# Decap.net
KiCad netlist of a schematic drawn in Altium Designer
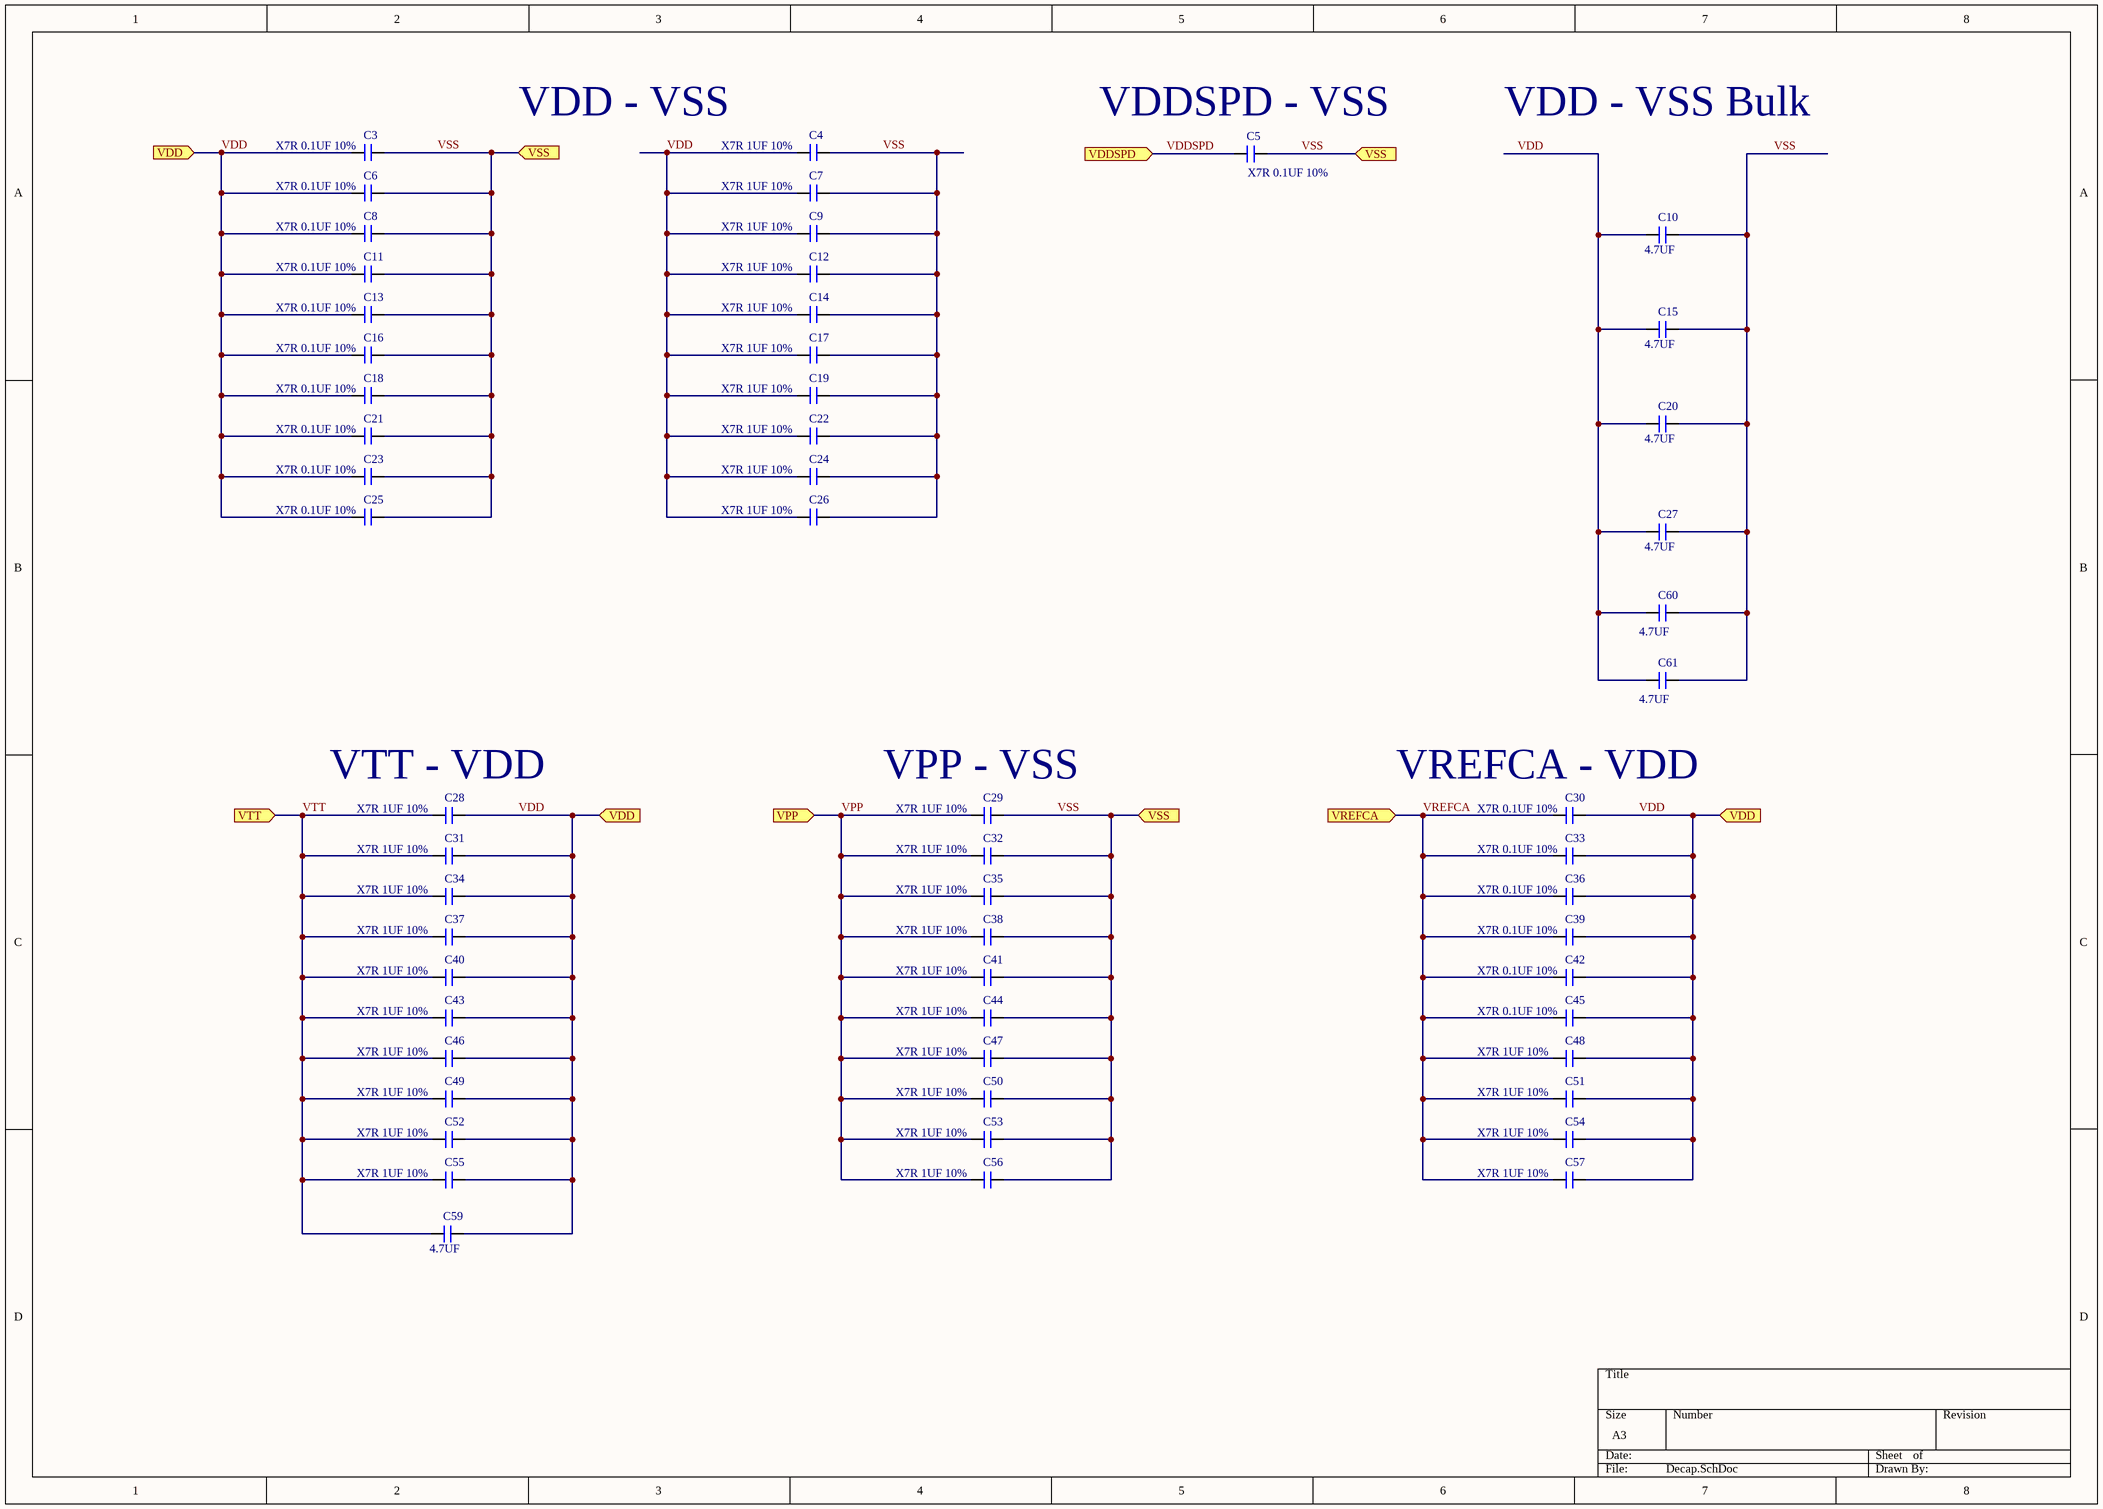
[diagram p0: Decap.SchDoc]

(export (version "E")
  (design (tool "Eeschema 10.0.6"))
  (components
    (comp (ref "C3")
      (value "Capacitor 0402")
      (footprint "Capacitor 0402")
      (fields
        (field (name "MANUFACTURER") "Vishay")
        (field (name "MANUFACTURER PART NUMBER") "CRCW060310K0FKEA")
        (field (name "TOLERANCE") "1%")
        (field (name "CAPACITANCE") "X7R 0.1UF 10%")
      )
      (libsource (lib "RouterIntLib") (part "Capacitor 0201"))
    )
    (comp (ref "C4")
      (value "Capacitor 0402")
      (footprint "Capacitor 0402")
      (fields
        (field (name "MANUFACTURER") "Vishay")
        (field (name "MANUFACTURER PART NUMBER") "CRCW060310K0FKEA")
        (field (name "TOLERANCE") "1%")
        (field (name "CAPACITANCE") "X7R 1UF 10%")
      )
      (libsource (lib "RouterIntLib") (part "Capacitor 0201"))
    )
    (comp (ref "C5")
      (value "Capacitor 0402")
      (footprint "Capacitor 0402")
      (fields
        (field (name "MANUFACTURER") "Vishay")
        (field (name "MANUFACTURER PART NUMBER") "CRCW060310K0FKEA")
        (field (name "TOLERANCE") "1%")
        (field (name "CAPACITANCE") "X7R 0.1UF 10%")
      )
      (libsource (lib "RouterIntLib") (part "Capacitor 0201"))
    )
    (comp (ref "C6")
      (value "Capacitor 0402")
      (footprint "Capacitor 0402")
      (fields
        (field (name "MANUFACTURER") "Vishay")
        (field (name "MANUFACTURER PART NUMBER") "CRCW060310K0FKEA")
        (field (name "TOLERANCE") "1%")
        (field (name "CAPACITANCE") "X7R 0.1UF 10%")
      )
      (libsource (lib "RouterIntLib") (part "Capacitor 0201"))
    )
    (comp (ref "C7")
      (value "Capacitor 0402")
      (footprint "Capacitor 0402")
      (fields
        (field (name "MANUFACTURER") "Vishay")
        (field (name "MANUFACTURER PART NUMBER") "CRCW060310K0FKEA")
        (field (name "TOLERANCE") "1%")
        (field (name "CAPACITANCE") "X7R 1UF 10%")
      )
      (libsource (lib "RouterIntLib") (part "Capacitor 0201"))
    )
    (comp (ref "C8")
      (value "Capacitor 0402")
      (footprint "Capacitor 0402")
      (fields
        (field (name "MANUFACTURER") "Vishay")
        (field (name "MANUFACTURER PART NUMBER") "CRCW060310K0FKEA")
        (field (name "TOLERANCE") "1%")
        (field (name "CAPACITANCE") "X7R 0.1UF 10%")
      )
      (libsource (lib "RouterIntLib") (part "Capacitor 0201"))
    )
    (comp (ref "C9")
      (value "Capacitor 0402")
      (footprint "Capacitor 0402")
      (fields
        (field (name "MANUFACTURER") "Vishay")
        (field (name "MANUFACTURER PART NUMBER") "CRCW060310K0FKEA")
        (field (name "TOLERANCE") "1%")
        (field (name "CAPACITANCE") "X7R 1UF 10%")
      )
      (libsource (lib "RouterIntLib") (part "Capacitor 0201"))
    )
    (comp (ref "C10")
      (value "Capacitor 0603")
      (footprint "Capacitor 0603")
      (fields
        (field (name "MANUFACTURER") "Vishay")
        (field (name "MANUFACTURER PART NUMBER") "CRCW060310K0FKEA")
        (field (name "TOLERANCE") "1%")
        (field (name "CAPACITANCE") "4.7UF")
      )
      (libsource (lib "RouterIntLib") (part "Capacitor 0603"))
    )
    (comp (ref "C11")
      (value "Capacitor 0402")
      (footprint "Capacitor 0402")
      (fields
        (field (name "MANUFACTURER") "Vishay")
        (field (name "MANUFACTURER PART NUMBER") "CRCW060310K0FKEA")
        (field (name "TOLERANCE") "1%")
        (field (name "CAPACITANCE") "X7R 0.1UF 10%")
      )
      (libsource (lib "RouterIntLib") (part "Capacitor 0201"))
    )
    (comp (ref "C12")
      (value "Capacitor 0402")
      (footprint "Capacitor 0402")
      (fields
        (field (name "MANUFACTURER") "Vishay")
        (field (name "MANUFACTURER PART NUMBER") "CRCW060310K0FKEA")
        (field (name "TOLERANCE") "1%")
        (field (name "CAPACITANCE") "X7R 1UF 10%")
      )
      (libsource (lib "RouterIntLib") (part "Capacitor 0201"))
    )
    (comp (ref "C13")
      (value "Capacitor 0402")
      (footprint "Capacitor 0402")
      (fields
        (field (name "MANUFACTURER") "Vishay")
        (field (name "MANUFACTURER PART NUMBER") "CRCW060310K0FKEA")
        (field (name "TOLERANCE") "1%")
        (field (name "CAPACITANCE") "X7R 0.1UF 10%")
      )
      (libsource (lib "RouterIntLib") (part "Capacitor 0201"))
    )
    (comp (ref "C14")
      (value "Capacitor 0402")
      (footprint "Capacitor 0402")
      (fields
        (field (name "MANUFACTURER") "Vishay")
        (field (name "MANUFACTURER PART NUMBER") "CRCW060310K0FKEA")
        (field (name "TOLERANCE") "1%")
        (field (name "CAPACITANCE") "X7R 1UF 10%")
      )
      (libsource (lib "RouterIntLib") (part "Capacitor 0201"))
    )
    (comp (ref "C15")
      (value "Capacitor 0603")
      (footprint "Capacitor 0603")
      (fields
        (field (name "MANUFACTURER") "Vishay")
        (field (name "MANUFACTURER PART NUMBER") "CRCW060310K0FKEA")
        (field (name "TOLERANCE") "1%")
        (field (name "CAPACITANCE") "4.7UF")
      )
      (libsource (lib "RouterIntLib") (part "Capacitor 0603"))
    )
    (comp (ref "C16")
      (value "Capacitor 0402")
      (footprint "Capacitor 0402")
      (fields
        (field (name "MANUFACTURER") "Vishay")
        (field (name "MANUFACTURER PART NUMBER") "CRCW060310K0FKEA")
        (field (name "TOLERANCE") "1%")
        (field (name "CAPACITANCE") "X7R 0.1UF 10%")
      )
      (libsource (lib "RouterIntLib") (part "Capacitor 0201"))
    )
    (comp (ref "C17")
      (value "Capacitor 0402")
      (footprint "Capacitor 0402")
      (fields
        (field (name "MANUFACTURER") "Vishay")
        (field (name "MANUFACTURER PART NUMBER") "CRCW060310K0FKEA")
        (field (name "TOLERANCE") "1%")
        (field (name "CAPACITANCE") "X7R 1UF 10%")
      )
      (libsource (lib "RouterIntLib") (part "Capacitor 0201"))
    )
    (comp (ref "C18")
      (value "Capacitor 0402")
      (footprint "Capacitor 0402")
      (fields
        (field (name "MANUFACTURER") "Vishay")
        (field (name "MANUFACTURER PART NUMBER") "CRCW060310K0FKEA")
        (field (name "TOLERANCE") "1%")
        (field (name "CAPACITANCE") "X7R 0.1UF 10%")
      )
      (libsource (lib "RouterIntLib") (part "Capacitor 0201"))
    )
    (comp (ref "C19")
      (value "Capacitor 0402")
      (footprint "Capacitor 0402")
      (fields
        (field (name "MANUFACTURER") "Vishay")
        (field (name "MANUFACTURER PART NUMBER") "CRCW060310K0FKEA")
        (field (name "TOLERANCE") "1%")
        (field (name "CAPACITANCE") "X7R 1UF 10%")
      )
      (libsource (lib "RouterIntLib") (part "Capacitor 0201"))
    )
    (comp (ref "C20")
      (value "Capacitor 0603")
      (footprint "Capacitor 0603")
      (fields
        (field (name "MANUFACTURER") "Vishay")
        (field (name "MANUFACTURER PART NUMBER") "CRCW060310K0FKEA")
        (field (name "TOLERANCE") "1%")
        (field (name "CAPACITANCE") "4.7UF")
      )
      (libsource (lib "RouterIntLib") (part "Capacitor 0603"))
    )
    (comp (ref "C21")
      (value "Capacitor 0402")
      (footprint "Capacitor 0402")
      (fields
        (field (name "MANUFACTURER") "Vishay")
        (field (name "MANUFACTURER PART NUMBER") "CRCW060310K0FKEA")
        (field (name "TOLERANCE") "1%")
        (field (name "CAPACITANCE") "X7R 0.1UF 10%")
      )
      (libsource (lib "RouterIntLib") (part "Capacitor 0201"))
    )
    (comp (ref "C22")
      (value "Capacitor 0402")
      (footprint "Capacitor 0402")
      (fields
        (field (name "MANUFACTURER") "Vishay")
        (field (name "MANUFACTURER PART NUMBER") "CRCW060310K0FKEA")
        (field (name "TOLERANCE") "1%")
        (field (name "CAPACITANCE") "X7R 1UF 10%")
      )
      (libsource (lib "RouterIntLib") (part "Capacitor 0201"))
    )
    (comp (ref "C23")
      (value "Capacitor 0402")
      (footprint "Capacitor 0402")
      (fields
        (field (name "MANUFACTURER") "Vishay")
        (field (name "MANUFACTURER PART NUMBER") "CRCW060310K0FKEA")
        (field (name "TOLERANCE") "1%")
        (field (name "CAPACITANCE") "X7R 0.1UF 10%")
      )
      (libsource (lib "RouterIntLib") (part "Capacitor 0201"))
    )
    (comp (ref "C24")
      (value "Capacitor 0402")
      (footprint "Capacitor 0402")
      (fields
        (field (name "MANUFACTURER") "Vishay")
        (field (name "MANUFACTURER PART NUMBER") "CRCW060310K0FKEA")
        (field (name "TOLERANCE") "1%")
        (field (name "CAPACITANCE") "X7R 1UF 10%")
      )
      (libsource (lib "RouterIntLib") (part "Capacitor 0201"))
    )
    (comp (ref "C25")
      (value "Capacitor 0402")
      (footprint "Capacitor 0402")
      (fields
        (field (name "MANUFACTURER") "Vishay")
        (field (name "MANUFACTURER PART NUMBER") "CRCW060310K0FKEA")
        (field (name "TOLERANCE") "1%")
        (field (name "CAPACITANCE") "X7R 0.1UF 10%")
      )
      (libsource (lib "RouterIntLib") (part "Capacitor 0201"))
    )
    (comp (ref "C26")
      (value "Capacitor 0402")
      (footprint "Capacitor 0402")
      (fields
        (field (name "MANUFACTURER") "Vishay")
        (field (name "MANUFACTURER PART NUMBER") "CRCW060310K0FKEA")
        (field (name "TOLERANCE") "1%")
        (field (name "CAPACITANCE") "X7R 1UF 10%")
      )
      (libsource (lib "RouterIntLib") (part "Capacitor 0201"))
    )
    (comp (ref "C27")
      (value "Capacitor 0603")
      (footprint "Capacitor 0603")
      (fields
        (field (name "MANUFACTURER") "Vishay")
        (field (name "MANUFACTURER PART NUMBER") "CRCW060310K0FKEA")
        (field (name "TOLERANCE") "1%")
        (field (name "CAPACITANCE") "4.7UF")
      )
      (libsource (lib "RouterIntLib") (part "Capacitor 0603"))
    )
    (comp (ref "C28")
      (value "Capacitor 0402")
      (footprint "Capacitor 0402")
      (fields
        (field (name "MANUFACTURER") "Vishay")
        (field (name "MANUFACTURER PART NUMBER") "CRCW060310K0FKEA")
        (field (name "TOLERANCE") "1%")
        (field (name "CAPACITANCE") "X7R 1UF 10%")
      )
      (libsource (lib "RouterIntLib") (part "Capacitor 0201"))
    )
    (comp (ref "C29")
      (value "Capacitor 0402")
      (footprint "Capacitor 0402")
      (fields
        (field (name "MANUFACTURER") "Vishay")
        (field (name "MANUFACTURER PART NUMBER") "CRCW060310K0FKEA")
        (field (name "TOLERANCE") "1%")
        (field (name "CAPACITANCE") "X7R 1UF 10%")
      )
      (libsource (lib "RouterIntLib") (part "Capacitor 0201"))
    )
    (comp (ref "C30")
      (value "Capacitor 0402")
      (footprint "Capacitor 0402")
      (fields
        (field (name "MANUFACTURER") "Vishay")
        (field (name "MANUFACTURER PART NUMBER") "CRCW060310K0FKEA")
        (field (name "TOLERANCE") "1%")
        (field (name "CAPACITANCE") "X7R 0.1UF 10%")
      )
      (libsource (lib "RouterIntLib") (part "Capacitor 0201"))
    )
    (comp (ref "C31")
      (value "Capacitor 0402")
      (footprint "Capacitor 0402")
      (fields
        (field (name "MANUFACTURER") "Vishay")
        (field (name "MANUFACTURER PART NUMBER") "CRCW060310K0FKEA")
        (field (name "TOLERANCE") "1%")
        (field (name "CAPACITANCE") "X7R 1UF 10%")
      )
      (libsource (lib "RouterIntLib") (part "Capacitor 0201"))
    )
    (comp (ref "C32")
      (value "Capacitor 0402")
      (footprint "Capacitor 0402")
      (fields
        (field (name "MANUFACTURER") "Vishay")
        (field (name "MANUFACTURER PART NUMBER") "CRCW060310K0FKEA")
        (field (name "TOLERANCE") "1%")
        (field (name "CAPACITANCE") "X7R 1UF 10%")
      )
      (libsource (lib "RouterIntLib") (part "Capacitor 0201"))
    )
    (comp (ref "C33")
      (value "Capacitor 0402")
      (footprint "Capacitor 0402")
      (fields
        (field (name "MANUFACTURER") "Vishay")
        (field (name "MANUFACTURER PART NUMBER") "CRCW060310K0FKEA")
        (field (name "TOLERANCE") "1%")
        (field (name "CAPACITANCE") "X7R 0.1UF 10%")
      )
      (libsource (lib "RouterIntLib") (part "Capacitor 0201"))
    )
    (comp (ref "C34")
      (value "Capacitor 0402")
      (footprint "Capacitor 0402")
      (fields
        (field (name "MANUFACTURER") "Vishay")
        (field (name "MANUFACTURER PART NUMBER") "CRCW060310K0FKEA")
        (field (name "TOLERANCE") "1%")
        (field (name "CAPACITANCE") "X7R 1UF 10%")
      )
      (libsource (lib "RouterIntLib") (part "Capacitor 0201"))
    )
    (comp (ref "C35")
      (value "Capacitor 0402")
      (footprint "Capacitor 0402")
      (fields
        (field (name "MANUFACTURER") "Vishay")
        (field (name "MANUFACTURER PART NUMBER") "CRCW060310K0FKEA")
        (field (name "TOLERANCE") "1%")
        (field (name "CAPACITANCE") "X7R 1UF 10%")
      )
      (libsource (lib "RouterIntLib") (part "Capacitor 0201"))
    )
    (comp (ref "C36")
      (value "Capacitor 0402")
      (footprint "Capacitor 0402")
      (fields
        (field (name "MANUFACTURER") "Vishay")
        (field (name "MANUFACTURER PART NUMBER") "CRCW060310K0FKEA")
        (field (name "TOLERANCE") "1%")
        (field (name "CAPACITANCE") "X7R 0.1UF 10%")
      )
      (libsource (lib "RouterIntLib") (part "Capacitor 0201"))
    )
    (comp (ref "C37")
      (value "Capacitor 0402")
      (footprint "Capacitor 0402")
      (fields
        (field (name "MANUFACTURER") "Vishay")
        (field (name "MANUFACTURER PART NUMBER") "CRCW060310K0FKEA")
        (field (name "TOLERANCE") "1%")
        (field (name "CAPACITANCE") "X7R 1UF 10%")
      )
      (libsource (lib "RouterIntLib") (part "Capacitor 0201"))
    )
    (comp (ref "C38")
      (value "Capacitor 0402")
      (footprint "Capacitor 0402")
      (fields
        (field (name "MANUFACTURER") "Vishay")
        (field (name "MANUFACTURER PART NUMBER") "CRCW060310K0FKEA")
        (field (name "TOLERANCE") "1%")
        (field (name "CAPACITANCE") "X7R 1UF 10%")
      )
      (libsource (lib "RouterIntLib") (part "Capacitor 0201"))
    )
    (comp (ref "C39")
      (value "Capacitor 0402")
      (footprint "Capacitor 0402")
      (fields
        (field (name "MANUFACTURER") "Vishay")
        (field (name "MANUFACTURER PART NUMBER") "CRCW060310K0FKEA")
        (field (name "TOLERANCE") "1%")
        (field (name "CAPACITANCE") "X7R 0.1UF 10%")
      )
      (libsource (lib "RouterIntLib") (part "Capacitor 0201"))
    )
    (comp (ref "C40")
      (value "Capacitor 0402")
      (footprint "Capacitor 0402")
      (fields
        (field (name "MANUFACTURER") "Vishay")
        (field (name "MANUFACTURER PART NUMBER") "CRCW060310K0FKEA")
        (field (name "TOLERANCE") "1%")
        (field (name "CAPACITANCE") "X7R 1UF 10%")
      )
      (libsource (lib "RouterIntLib") (part "Capacitor 0201"))
    )
    (comp (ref "C41")
      (value "Capacitor 0402")
      (footprint "Capacitor 0402")
      (fields
        (field (name "MANUFACTURER") "Vishay")
        (field (name "MANUFACTURER PART NUMBER") "CRCW060310K0FKEA")
        (field (name "TOLERANCE") "1%")
        (field (name "CAPACITANCE") "X7R 1UF 10%")
      )
      (libsource (lib "RouterIntLib") (part "Capacitor 0201"))
    )
    (comp (ref "C42")
      (value "Capacitor 0402")
      (footprint "Capacitor 0402")
      (fields
        (field (name "MANUFACTURER") "Vishay")
        (field (name "MANUFACTURER PART NUMBER") "CRCW060310K0FKEA")
        (field (name "TOLERANCE") "1%")
        (field (name "CAPACITANCE") "X7R 0.1UF 10%")
      )
      (libsource (lib "RouterIntLib") (part "Capacitor 0201"))
    )
    (comp (ref "C43")
      (value "Capacitor 0402")
      (footprint "Capacitor 0402")
      (fields
        (field (name "MANUFACTURER") "Vishay")
        (field (name "MANUFACTURER PART NUMBER") "CRCW060310K0FKEA")
        (field (name "TOLERANCE") "1%")
        (field (name "CAPACITANCE") "X7R 1UF 10%")
      )
      (libsource (lib "RouterIntLib") (part "Capacitor 0201"))
    )
    (comp (ref "C44")
      (value "Capacitor 0402")
      (footprint "Capacitor 0402")
      (fields
        (field (name "MANUFACTURER") "Vishay")
        (field (name "MANUFACTURER PART NUMBER") "CRCW060310K0FKEA")
        (field (name "TOLERANCE") "1%")
        (field (name "CAPACITANCE") "X7R 1UF 10%")
      )
      (libsource (lib "RouterIntLib") (part "Capacitor 0201"))
    )
    (comp (ref "C45")
      (value "Capacitor 0402")
      (footprint "Capacitor 0402")
      (fields
        (field (name "MANUFACTURER") "Vishay")
        (field (name "MANUFACTURER PART NUMBER") "CRCW060310K0FKEA")
        (field (name "TOLERANCE") "1%")
        (field (name "CAPACITANCE") "X7R 0.1UF 10%")
      )
      (libsource (lib "RouterIntLib") (part "Capacitor 0201"))
    )
    (comp (ref "C46")
      (value "Capacitor 0402")
      (footprint "Capacitor 0402")
      (fields
        (field (name "MANUFACTURER") "Vishay")
        (field (name "MANUFACTURER PART NUMBER") "CRCW060310K0FKEA")
        (field (name "TOLERANCE") "1%")
        (field (name "CAPACITANCE") "X7R 1UF 10%")
      )
      (libsource (lib "RouterIntLib") (part "Capacitor 0201"))
    )
    (comp (ref "C47")
      (value "Capacitor 0402")
      (footprint "Capacitor 0402")
      (fields
        (field (name "MANUFACTURER") "Vishay")
        (field (name "MANUFACTURER PART NUMBER") "CRCW060310K0FKEA")
        (field (name "TOLERANCE") "1%")
        (field (name "CAPACITANCE") "X7R 1UF 10%")
      )
      (libsource (lib "RouterIntLib") (part "Capacitor 0201"))
    )
    (comp (ref "C48")
      (value "Capacitor 0402")
      (footprint "Capacitor 0402")
      (fields
        (field (name "MANUFACTURER") "Vishay")
        (field (name "MANUFACTURER PART NUMBER") "CRCW060310K0FKEA")
        (field (name "TOLERANCE") "1%")
        (field (name "CAPACITANCE") "X7R 1UF 10%")
      )
      (libsource (lib "RouterIntLib") (part "Capacitor 0201"))
    )
    (comp (ref "C49")
      (value "Capacitor 0402")
      (footprint "Capacitor 0402")
      (fields
        (field (name "MANUFACTURER") "Vishay")
        (field (name "MANUFACTURER PART NUMBER") "CRCW060310K0FKEA")
        (field (name "TOLERANCE") "1%")
        (field (name "CAPACITANCE") "X7R 1UF 10%")
      )
      (libsource (lib "RouterIntLib") (part "Capacitor 0201"))
    )
    (comp (ref "C50")
      (value "Capacitor 0402")
      (footprint "Capacitor 0402")
      (fields
        (field (name "MANUFACTURER") "Vishay")
        (field (name "MANUFACTURER PART NUMBER") "CRCW060310K0FKEA")
        (field (name "TOLERANCE") "1%")
        (field (name "CAPACITANCE") "X7R 1UF 10%")
      )
      (libsource (lib "RouterIntLib") (part "Capacitor 0201"))
    )
    (comp (ref "C51")
      (value "Capacitor 0402")
      (footprint "Capacitor 0402")
      (fields
        (field (name "MANUFACTURER") "Vishay")
        (field (name "MANUFACTURER PART NUMBER") "CRCW060310K0FKEA")
        (field (name "TOLERANCE") "1%")
        (field (name "CAPACITANCE") "X7R 1UF 10%")
      )
      (libsource (lib "RouterIntLib") (part "Capacitor 0201"))
    )
    (comp (ref "C52")
      (value "Capacitor 0402")
      (footprint "Capacitor 0402")
      (fields
        (field (name "MANUFACTURER") "Vishay")
        (field (name "MANUFACTURER PART NUMBER") "CRCW060310K0FKEA")
        (field (name "TOLERANCE") "1%")
        (field (name "CAPACITANCE") "X7R 1UF 10%")
      )
      (libsource (lib "RouterIntLib") (part "Capacitor 0201"))
    )
    (comp (ref "C53")
      (value "Capacitor 0402")
      (footprint "Capacitor 0402")
      (fields
        (field (name "MANUFACTURER") "Vishay")
        (field (name "MANUFACTURER PART NUMBER") "CRCW060310K0FKEA")
        (field (name "TOLERANCE") "1%")
        (field (name "CAPACITANCE") "X7R 1UF 10%")
      )
      (libsource (lib "RouterIntLib") (part "Capacitor 0201"))
    )
    (comp (ref "C54")
      (value "Capacitor 0402")
      (footprint "Capacitor 0402")
      (fields
        (field (name "MANUFACTURER") "Vishay")
        (field (name "MANUFACTURER PART NUMBER") "CRCW060310K0FKEA")
        (field (name "TOLERANCE") "1%")
        (field (name "CAPACITANCE") "X7R 1UF 10%")
      )
      (libsource (lib "RouterIntLib") (part "Capacitor 0201"))
    )
    (comp (ref "C55")
      (value "Capacitor 0402")
      (footprint "Capacitor 0402")
      (fields
        (field (name "MANUFACTURER") "Vishay")
        (field (name "MANUFACTURER PART NUMBER") "CRCW060310K0FKEA")
        (field (name "TOLERANCE") "1%")
        (field (name "CAPACITANCE") "X7R 1UF 10%")
      )
      (libsource (lib "RouterIntLib") (part "Capacitor 0201"))
    )
    (comp (ref "C56")
      (value "Capacitor 0402")
      (footprint "Capacitor 0402")
      (fields
        (field (name "MANUFACTURER") "Vishay")
        (field (name "MANUFACTURER PART NUMBER") "CRCW060310K0FKEA")
        (field (name "TOLERANCE") "1%")
        (field (name "CAPACITANCE") "X7R 1UF 10%")
      )
      (libsource (lib "RouterIntLib") (part "Capacitor 0201"))
    )
    (comp (ref "C57")
      (value "Capacitor 0402")
      (footprint "Capacitor 0402")
      (fields
        (field (name "MANUFACTURER") "Vishay")
        (field (name "MANUFACTURER PART NUMBER") "CRCW060310K0FKEA")
        (field (name "TOLERANCE") "1%")
        (field (name "CAPACITANCE") "X7R 1UF 10%")
      )
      (libsource (lib "RouterIntLib") (part "Capacitor 0201"))
    )
    (comp (ref "C59")
      (value "Capacitor 0603")
      (footprint "Capacitor 0603")
      (fields
        (field (name "MANUFACTURER") "Vishay")
        (field (name "MANUFACTURER PART NUMBER") "CRCW060310K0FKEA")
        (field (name "TOLERANCE") "1%")
        (field (name "CAPACITANCE") "4.7UF")
      )
      (libsource (lib "RouterIntLib") (part "Capacitor 0603"))
    )
    (comp (ref "C60")
      (value "Capacitor 0603")
      (footprint "Capacitor 0603")
      (fields
        (field (name "MANUFACTURER") "Vishay")
        (field (name "MANUFACTURER PART NUMBER") "CRCW060310K0FKEA")
        (field (name "TOLERANCE") "1%")
        (field (name "CAPACITANCE") "4.7UF")
      )
      (libsource (lib "RouterIntLib") (part "Capacitor 0603"))
    )
    (comp (ref "C61")
      (value "Capacitor 0603")
      (footprint "Capacitor 0603")
      (fields
        (field (name "MANUFACTURER") "Vishay")
        (field (name "MANUFACTURER PART NUMBER") "CRCW060310K0FKEA")
        (field (name "TOLERANCE") "1%")
        (field (name "CAPACITANCE") "4.7UF")
      )
      (libsource (lib "RouterIntLib") (part "Capacitor 0603"))
    )
  )
  (nets
    (net (code "1") (name "/VDD") (class "Default")
      (node (ref "C10") (pin "1") (pinfunction "1_1") (pintype "passive"))
      (node (ref "C11") (pin "1") (pinfunction "1_1") (pintype "passive"))
      (node (ref "C12") (pin "1") (pinfunction "1_1") (pintype "passive"))
      (node (ref "C13") (pin "1") (pinfunction "1_1") (pintype "passive"))
      (node (ref "C14") (pin "1") (pinfunction "1_1") (pintype "passive"))
      (node (ref "C15") (pin "1") (pinfunction "1_1") (pintype "passive"))
      (node (ref "C16") (pin "1") (pinfunction "1_1") (pintype "passive"))
      (node (ref "C17") (pin "1") (pinfunction "1_1") (pintype "passive"))
      (node (ref "C18") (pin "1") (pinfunction "1_1") (pintype "passive"))
      (node (ref "C19") (pin "1") (pinfunction "1_1") (pintype "passive"))
      (node (ref "C20") (pin "1") (pinfunction "1_1") (pintype "passive"))
      (node (ref "C21") (pin "1") (pinfunction "1_1") (pintype "passive"))
      (node (ref "C22") (pin "1") (pinfunction "1_1") (pintype "passive"))
      (node (ref "C23") (pin "1") (pinfunction "1_1") (pintype "passive"))
      (node (ref "C24") (pin "1") (pinfunction "1_1") (pintype "passive"))
      (node (ref "C25") (pin "1") (pinfunction "1_1") (pintype "passive"))
      (node (ref "C26") (pin "1") (pinfunction "1_1") (pintype "passive"))
      (node (ref "C27") (pin "1") (pinfunction "1_1") (pintype "passive"))
      (node (ref "C28") (pin "2") (pinfunction "2_2") (pintype "passive"))
      (node (ref "C3") (pin "1") (pinfunction "1_1") (pintype "passive"))
      (node (ref "C30") (pin "2") (pinfunction "2_2") (pintype "passive"))
      (node (ref "C31") (pin "2") (pinfunction "2_2") (pintype "passive"))
      (node (ref "C33") (pin "2") (pinfunction "2_2") (pintype "passive"))
      (node (ref "C34") (pin "2") (pinfunction "2_2") (pintype "passive"))
      (node (ref "C36") (pin "2") (pinfunction "2_2") (pintype "passive"))
      (node (ref "C37") (pin "2") (pinfunction "2_2") (pintype "passive"))
      (node (ref "C39") (pin "2") (pinfunction "2_2") (pintype "passive"))
      (node (ref "C4") (pin "1") (pinfunction "1_1") (pintype "passive"))
      (node (ref "C40") (pin "2") (pinfunction "2_2") (pintype "passive"))
      (node (ref "C42") (pin "2") (pinfunction "2_2") (pintype "passive"))
      (node (ref "C43") (pin "2") (pinfunction "2_2") (pintype "passive"))
      (node (ref "C45") (pin "2") (pinfunction "2_2") (pintype "passive"))
      (node (ref "C46") (pin "2") (pinfunction "2_2") (pintype "passive"))
      (node (ref "C48") (pin "2") (pinfunction "2_2") (pintype "passive"))
      (node (ref "C49") (pin "2") (pinfunction "2_2") (pintype "passive"))
      (node (ref "C51") (pin "2") (pinfunction "2_2") (pintype "passive"))
      (node (ref "C52") (pin "2") (pinfunction "2_2") (pintype "passive"))
      (node (ref "C54") (pin "2") (pinfunction "2_2") (pintype "passive"))
      (node (ref "C55") (pin "2") (pinfunction "2_2") (pintype "passive"))
      (node (ref "C57") (pin "2") (pinfunction "2_2") (pintype "passive"))
      (node (ref "C59") (pin "2") (pinfunction "2_2") (pintype "passive"))
      (node (ref "C6") (pin "1") (pinfunction "1_1") (pintype "passive"))
      (node (ref "C60") (pin "1") (pinfunction "1_1") (pintype "passive"))
      (node (ref "C61") (pin "1") (pinfunction "1_1") (pintype "passive"))
      (node (ref "C7") (pin "1") (pinfunction "1_1") (pintype "passive"))
      (node (ref "C8") (pin "1") (pinfunction "1_1") (pintype "passive"))
      (node (ref "C9") (pin "1") (pinfunction "1_1") (pintype "passive"))
    )
    (net (code "2") (name "/VDDSPD") (class "Default")
      (node (ref "C5") (pin "1") (pinfunction "1_1") (pintype "passive"))
    )
    (net (code "3") (name "/VPP") (class "Default")
      (node (ref "C29") (pin "1") (pinfunction "1_1") (pintype "passive"))
      (node (ref "C32") (pin "1") (pinfunction "1_1") (pintype "passive"))
      (node (ref "C35") (pin "1") (pinfunction "1_1") (pintype "passive"))
      (node (ref "C38") (pin "1") (pinfunction "1_1") (pintype "passive"))
      (node (ref "C41") (pin "1") (pinfunction "1_1") (pintype "passive"))
      (node (ref "C44") (pin "1") (pinfunction "1_1") (pintype "passive"))
      (node (ref "C47") (pin "1") (pinfunction "1_1") (pintype "passive"))
      (node (ref "C50") (pin "1") (pinfunction "1_1") (pintype "passive"))
      (node (ref "C53") (pin "1") (pinfunction "1_1") (pintype "passive"))
      (node (ref "C56") (pin "1") (pinfunction "1_1") (pintype "passive"))
    )
    (net (code "4") (name "/VREFCA") (class "Default")
      (node (ref "C30") (pin "1") (pinfunction "1_1") (pintype "passive"))
      (node (ref "C33") (pin "1") (pinfunction "1_1") (pintype "passive"))
      (node (ref "C36") (pin "1") (pinfunction "1_1") (pintype "passive"))
      (node (ref "C39") (pin "1") (pinfunction "1_1") (pintype "passive"))
      (node (ref "C42") (pin "1") (pinfunction "1_1") (pintype "passive"))
      (node (ref "C45") (pin "1") (pinfunction "1_1") (pintype "passive"))
      (node (ref "C48") (pin "1") (pinfunction "1_1") (pintype "passive"))
      (node (ref "C51") (pin "1") (pinfunction "1_1") (pintype "passive"))
      (node (ref "C54") (pin "1") (pinfunction "1_1") (pintype "passive"))
      (node (ref "C57") (pin "1") (pinfunction "1_1") (pintype "passive"))
    )
    (net (code "5") (name "/VSS") (class "Default")
      (node (ref "C10") (pin "2") (pinfunction "2_2") (pintype "passive"))
      (node (ref "C11") (pin "2") (pinfunction "2_2") (pintype "passive"))
      (node (ref "C12") (pin "2") (pinfunction "2_2") (pintype "passive"))
      (node (ref "C13") (pin "2") (pinfunction "2_2") (pintype "passive"))
      (node (ref "C14") (pin "2") (pinfunction "2_2") (pintype "passive"))
      (node (ref "C15") (pin "2") (pinfunction "2_2") (pintype "passive"))
      (node (ref "C16") (pin "2") (pinfunction "2_2") (pintype "passive"))
      (node (ref "C17") (pin "2") (pinfunction "2_2") (pintype "passive"))
      (node (ref "C18") (pin "2") (pinfunction "2_2") (pintype "passive"))
      (node (ref "C19") (pin "2") (pinfunction "2_2") (pintype "passive"))
      (node (ref "C20") (pin "2") (pinfunction "2_2") (pintype "passive"))
      (node (ref "C21") (pin "2") (pinfunction "2_2") (pintype "passive"))
      (node (ref "C22") (pin "2") (pinfunction "2_2") (pintype "passive"))
      (node (ref "C23") (pin "2") (pinfunction "2_2") (pintype "passive"))
      (node (ref "C24") (pin "2") (pinfunction "2_2") (pintype "passive"))
      (node (ref "C25") (pin "2") (pinfunction "2_2") (pintype "passive"))
      (node (ref "C26") (pin "2") (pinfunction "2_2") (pintype "passive"))
      (node (ref "C27") (pin "2") (pinfunction "2_2") (pintype "passive"))
      (node (ref "C29") (pin "2") (pinfunction "2_2") (pintype "passive"))
      (node (ref "C3") (pin "2") (pinfunction "2_2") (pintype "passive"))
      (node (ref "C32") (pin "2") (pinfunction "2_2") (pintype "passive"))
      (node (ref "C35") (pin "2") (pinfunction "2_2") (pintype "passive"))
      (node (ref "C38") (pin "2") (pinfunction "2_2") (pintype "passive"))
      (node (ref "C4") (pin "2") (pinfunction "2_2") (pintype "passive"))
      (node (ref "C41") (pin "2") (pinfunction "2_2") (pintype "passive"))
      (node (ref "C44") (pin "2") (pinfunction "2_2") (pintype "passive"))
      (node (ref "C47") (pin "2") (pinfunction "2_2") (pintype "passive"))
      (node (ref "C5") (pin "2") (pinfunction "2_2") (pintype "passive"))
      (node (ref "C50") (pin "2") (pinfunction "2_2") (pintype "passive"))
      (node (ref "C53") (pin "2") (pinfunction "2_2") (pintype "passive"))
      (node (ref "C56") (pin "2") (pinfunction "2_2") (pintype "passive"))
      (node (ref "C6") (pin "2") (pinfunction "2_2") (pintype "passive"))
      (node (ref "C60") (pin "2") (pinfunction "2_2") (pintype "passive"))
      (node (ref "C61") (pin "2") (pinfunction "2_2") (pintype "passive"))
      (node (ref "C7") (pin "2") (pinfunction "2_2") (pintype "passive"))
      (node (ref "C8") (pin "2") (pinfunction "2_2") (pintype "passive"))
      (node (ref "C9") (pin "2") (pinfunction "2_2") (pintype "passive"))
    )
    (net (code "6") (name "/VTT") (class "Default")
      (node (ref "C28") (pin "1") (pinfunction "1_1") (pintype "passive"))
      (node (ref "C31") (pin "1") (pinfunction "1_1") (pintype "passive"))
      (node (ref "C34") (pin "1") (pinfunction "1_1") (pintype "passive"))
      (node (ref "C37") (pin "1") (pinfunction "1_1") (pintype "passive"))
      (node (ref "C40") (pin "1") (pinfunction "1_1") (pintype "passive"))
      (node (ref "C43") (pin "1") (pinfunction "1_1") (pintype "passive"))
      (node (ref "C46") (pin "1") (pinfunction "1_1") (pintype "passive"))
      (node (ref "C49") (pin "1") (pinfunction "1_1") (pintype "passive"))
      (node (ref "C52") (pin "1") (pinfunction "1_1") (pintype "passive"))
      (node (ref "C55") (pin "1") (pinfunction "1_1") (pintype "passive"))
      (node (ref "C59") (pin "1") (pinfunction "1_1") (pintype "passive"))
    )
  )
)
